# FLASH.net
KiCad netlist of a schematic drawn in Altium Designer
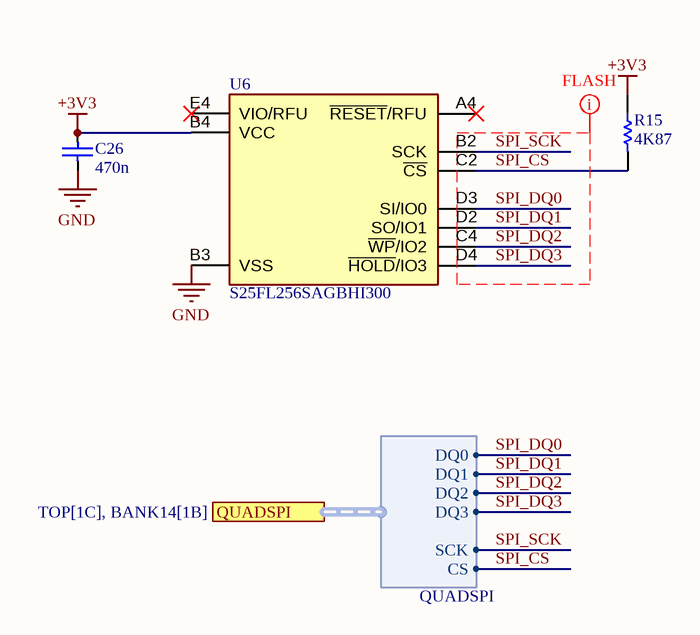
[diagram p0: FLASH.SchDoc]

(export (version "E")
  (design (tool "Eeschema 10.0.6"))
  (components
    (comp (ref "C26")
      (value "470n")
      (footprint "pcblib1:FP-C1005-050-0_05-IPC_C")
      (description "MLCC 470nF ±10% 25V X5R SMD 0402")
      (fields (field (name "VOLTAGE") "25V") (field (name "TOLERANCE") "10%"))
      (libsource (lib "Schlib1") (part "C1005X5R1E474K050BB"))
    )
    (comp (ref "R15")
      (value "4K87")
      (footprint "RESC1005X40X25LL05T10")
      (fields (field (name "PART NUMBER") "RC0402FR-074K87L") (field (name "MANUFACTURER") "Yageo / Phycomp"))
      (libsource (lib "Schlib1") (part "RC0402FR-074K87L"))
    )
    (comp (ref "U6")
      (value "S25FL256SAGBHI300")
      (footprint "BGA24C100P4X6_600X800X120")
      (description "Integrated Circuit")
      (fields (field (name "MOUSER PART NUMBER") "797-25FL256SAGBHI300"))
      (libsource (lib "Schlib1") (part "S25FL256SAGBHI200"))
    )
  )
  (nets
    (net (code "2") (name "+3V3") (class "Default")
      (node (ref "C26") (pin "1") (pinfunction "1_1") (pintype "passive"))
      (node (ref "R15") (pin "1") (pinfunction "1_1") (pintype "passive"))
      (node (ref "U6") (pin "B4") (pinfunction "VCC_B4") (pintype "passive"))
    )
    (net (code "3") (name "/SPI_CS") (class "Default")
      (node (ref "R15") (pin "2") (pinfunction "2_2") (pintype "passive"))
      (node (ref "U6") (pin "C2") (pinfunction "~{CS}_C2") (pintype "passive"))
    )
    (net (code "4") (name "/SPI_DQ0") (class "Default")
      (node (ref "U6") (pin "D3") (pinfunction "SI/IO0_D3") (pintype "passive"))
    )
    (net (code "5") (name "/SPI_DQ1") (class "Default")
      (node (ref "U6") (pin "D2") (pinfunction "SO/IO1_D2") (pintype "passive"))
    )
    (net (code "6") (name "/SPI_DQ2") (class "Default")
      (node (ref "U6") (pin "C4") (pinfunction "~{WP}/IO2_C4") (pintype "passive"))
    )
    (net (code "7") (name "/SPI_DQ3") (class "Default")
      (node (ref "U6") (pin "D4") (pinfunction "~{HOLD}/IO3_D4") (pintype "passive"))
    )
    (net (code "8") (name "/SPI_SCK") (class "Default")
      (node (ref "U6") (pin "B2") (pinfunction "SCK_B2") (pintype "passive"))
    )
    (net (code "10") (name "GND") (class "Default")
      (node (ref "C26") (pin "2") (pinfunction "2_2") (pintype "passive"))
      (node (ref "U6") (pin "B3") (pinfunction "VSS_B3") (pintype "passive"))
    )
    (net (code "11") (name "unconnected-(U6-DNU_1-PadB1)") (class "Default")
      (node (ref "U6") (pin "B1") (pinfunction "DNU_1_B1") (pintype "passive"))
    )
    (net (code "12") (name "unconnected-(U6-DNU_2-PadC1)") (class "Default")
      (node (ref "U6") (pin "C1") (pinfunction "DNU_2_C1") (pintype "passive"))
    )
    (net (code "13") (name "unconnected-(U6-DNU_3-PadD1)") (class "Default")
      (node (ref "U6") (pin "D1") (pinfunction "DNU_3_D1") (pintype "passive"))
    )
    (net (code "14") (name "unconnected-(U6-NC_1-PadA1)") (class "Default")
      (node (ref "U6") (pin "A1") (pinfunction "NC_1_A1") (pintype "passive"))
    )
    (net (code "15") (name "unconnected-(U6-NC_2-PadA2)") (class "Default")
      (node (ref "U6") (pin "A2") (pinfunction "NC_2_A2") (pintype "passive"))
    )
    (net (code "16") (name "unconnected-(U6-NC_3-PadA3)") (class "Default")
      (node (ref "U6") (pin "A3") (pinfunction "NC_3_A3") (pintype "passive"))
    )
    (net (code "17") (name "unconnected-(U6-NC_4-PadE1)") (class "Default")
      (node (ref "U6") (pin "E1") (pinfunction "NC_4_E1") (pintype "passive"))
    )
    (net (code "18") (name "unconnected-(U6-NC_5-PadE2)") (class "Default")
      (node (ref "U6") (pin "E2") (pinfunction "NC_5_E2") (pintype "passive"))
    )
    (net (code "19") (name "unconnected-(U6-NC_6-PadE3)") (class "Default")
      (node (ref "U6") (pin "E3") (pinfunction "NC_6_E3") (pintype "passive"))
    )
    (net (code "20") (name "unconnected-(U6-NC_7-PadF1)") (class "Default")
      (node (ref "U6") (pin "F1") (pinfunction "NC_7_F1") (pintype "passive"))
    )
    (net (code "21") (name "unconnected-(U6-NC_8-PadF2)") (class "Default")
      (node (ref "U6") (pin "F2") (pinfunction "NC_8_F2") (pintype "passive"))
    )
    (net (code "22") (name "unconnected-(U6-NC_9-PadF3)") (class "Default")
      (node (ref "U6") (pin "F3") (pinfunction "NC_9_F3") (pintype "passive"))
    )
    (net (code "23") (name "unconnected-(U6-NC_10-PadF4)") (class "Default")
      (node (ref "U6") (pin "F4") (pinfunction "NC_10_F4") (pintype "passive"))
    )
    (net (code "24") (name "unconnected-(U6-RFU-PadC3)") (class "Default")
      (node (ref "U6") (pin "C3") (pinfunction "RFU_C3") (pintype "passive"))
    )
    (net (code "25") (name "unconnected-(U6-VIO{slash}RFU-PadE4)") (class "Default")
      (node (ref "U6") (pin "E4") (pinfunction "VIO/RFU_E4") (pintype "passive+no_connect"))
    )
    (net (code "26") (name "unconnected-(U6-~{RESET}{slash}RFU-PadA4)") (class "Default")
      (node (ref "U6") (pin "A4") (pinfunction "~{RESET}/RFU_A4") (pintype "passive+no_connect"))
    )
  )
)
